# Core.net
KiCad netlist of a schematic drawn in Altium Designer
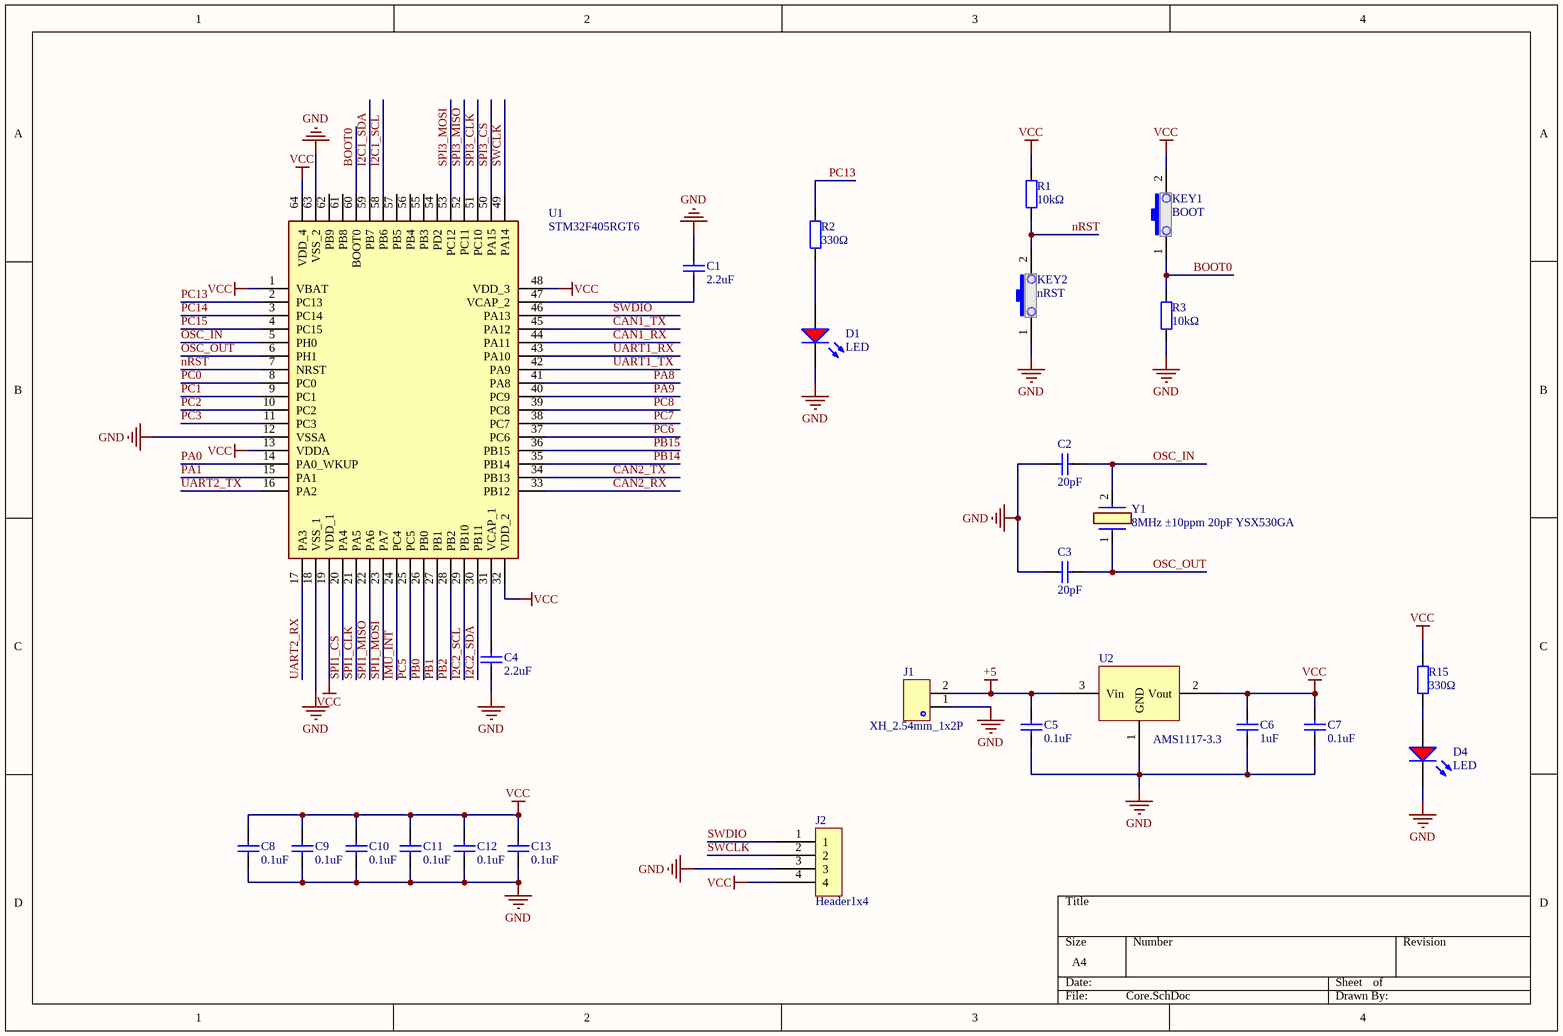
[diagram p0: Core.SchDoc]

(export (version "E")
  (design (tool "Eeschema 10.0.6"))
  (components
    (comp (ref "C1") (value "2.2uF") (footprint "C0603") (libsource (lib "NetTie") (part "Capacitor")))
    (comp (ref "C2") (value "20pF") (footprint "C0603") (libsource (lib "NetTie") (part "Capacitor")))
    (comp (ref "C3") (value "20pF") (footprint "C0603") (libsource (lib "NetTie") (part "Capacitor")))
    (comp (ref "C4") (value "2.2uF") (footprint "C0603") (libsource (lib "NetTie") (part "Capacitor")))
    (comp (ref "C5") (value "0.1uF") (footprint "C0603") (libsource (lib "NetTie") (part "Capacitor")))
    (comp (ref "C6") (value "1uF") (footprint "C0603") (libsource (lib "NetTie") (part "Capacitor")))
    (comp (ref "C7") (value "0.1uF") (footprint "C0603") (libsource (lib "NetTie") (part "Capacitor")))
    (comp (ref "C8") (value "0.1uF") (footprint "C0603") (libsource (lib "NetTie") (part "Capacitor")))
    (comp (ref "C9") (value "0.1uF") (footprint "C0603") (libsource (lib "NetTie") (part "Capacitor")))
    (comp (ref "C10") (value "0.1uF") (footprint "C0603") (libsource (lib "NetTie") (part "Capacitor")))
    (comp (ref "C11") (value "0.1uF") (footprint "C0603") (libsource (lib "NetTie") (part "Capacitor")))
    (comp (ref "C12") (value "0.1uF") (footprint "C0603") (libsource (lib "NetTie") (part "Capacitor")))
    (comp (ref "C13") (value "0.1uF") (footprint "C0603") (libsource (lib "NetTie") (part "Capacitor")))
    (comp (ref "D1")
      (value "LED")
      (footprint "0603_LED_S1")
      (description "发光二极管")
      (libsource (lib "LED") (part "0603 红灯"))
    )
    (comp (ref "D4")
      (value "LED")
      (footprint "0603_LED_S1")
      (description "发光二极管")
      (libsource (lib "LED") (part "0603 红灯"))
    )
    (comp (ref "J1")
      (value "XH_2.54mm_1x2P")
      (footprint "XH2.54mm1x2P弯插")
      (libsource (lib "NetTie") (part "XH_2.54mm_1x2P"))
    )
    (comp (ref "J2")
      (value "Header1x4")
      (footprint "Header 1x4p")
      (libsource (lib "Connectors") (part "Header1x4"))
    )
    (comp (ref "KEY1")
      (value "BOOT")
      (footprint "KEY_3*4")
      (description "C707339")
      (libsource (lib "NetTie") (part "KEY_3*4"))
    )
    (comp (ref "KEY2")
      (value "nRST")
      (footprint "KEY_3*4")
      (description "C707339")
      (libsource (lib "NetTie") (part "KEY_3*4"))
    )
    (comp (ref "R1") (value "10kΩ") (footprint "R0603") (libsource (lib "NetTie") (part "Resistor")))
    (comp (ref "R2") (value "330Ω") (footprint "R0603") (libsource (lib "") (part "Resistor_1")))
    (comp (ref "R3") (value "10kΩ") (footprint "R0603") (libsource (lib "NetTie") (part "Resistor")))
    (comp (ref "R15") (value "330Ω") (footprint "R0603") (libsource (lib "") (part "Resistor_1")))
    (comp (ref "U1")
      (value "STM32F405RGT6")
      (footprint "SamacSys:QFP50P1200X1200X160-64N")
      (description "Integrated Circuit")
      (fields
        (field (name "MANUFACTURER_PART_NUMBER") "STM32F405RGT6TR")
        (field (name "MOUSER PART NUMBER") "511-STM32F405RGT6TR")
      )
      (libsource (lib "*") (part "STM32F405RGT6TR"))
    )
    (comp (ref "U2")
      (value "AMS1117-3.3")
      (footprint "SOT-223")
      (description "C347222")
      (libsource (lib "PowerICs") (part "AMS1117-3.3"))
    )
    (comp (ref "Y1")
      (value "8MHz ±10ppm 20pF YSX530GA")
      (footprint "SamacSys:X503212MSB2GI")
      (description "Crystal or Oscillator")
      (fields (field (name "MANUFACTURER_PART_NUMBER") "X503212MSB2GI"))
      (libsource (lib "*") (part "X503212MSB2GI"))
    )
  )
  (nets
    (net (code "1") (name "+5") (class "Default")
      (node (ref "C5") (pin "2") (pinfunction "2_2") (pintype "passive"))
      (node (ref "J1") (pin "2") (pinfunction "2_2") (pintype "passive"))
      (node (ref "U2") (pin "3") (pinfunction "Vin_3") (pintype "passive"))
    )
    (net (code "2") (name "/BOOT0") (class "Default")
      (node (ref "KEY1") (pin "1") (pinfunction "1_1") (pintype "passive"))
      (node (ref "R3") (pin "2") (pinfunction "2_2") (pintype "passive"))
      (node (ref "U1") (pin "60") (pinfunction "BOOT0_60") (pintype "passive"))
    )
    (net (code "3") (name "/CAN1_RX") (class "Default")
      (node (ref "U1") (pin "44") (pinfunction "PA11_44") (pintype "passive"))
    )
    (net (code "4") (name "/CAN1_TX") (class "Default")
      (node (ref "U1") (pin "45") (pinfunction "PA12_45") (pintype "passive"))
    )
    (net (code "5") (name "/CAN2_RX") (class "Default")
      (node (ref "U1") (pin "33") (pinfunction "PB12_33") (pintype "passive"))
    )
    (net (code "6") (name "/CAN2_TX") (class "Default")
      (node (ref "U1") (pin "34") (pinfunction "PB13_34") (pintype "passive"))
    )
    (net (code "7") (name "/I2C1_SCL") (class "Default")
      (node (ref "U1") (pin "58") (pinfunction "PB6_58") (pintype "passive"))
    )
    (net (code "8") (name "/I2C1_SDA") (class "Default")
      (node (ref "U1") (pin "59") (pinfunction "PB7_59") (pintype "passive"))
    )
    (net (code "9") (name "/I2C2_SCL") (class "Default")
      (node (ref "U1") (pin "29") (pinfunction "PB10_29") (pintype "passive"))
    )
    (net (code "10") (name "/I2C2_SDA") (class "Default")
      (node (ref "U1") (pin "30") (pinfunction "PB11_30") (pintype "passive"))
    )
    (net (code "11") (name "/IMU_INT") (class "Default")
      (node (ref "U1") (pin "24") (pinfunction "PC4_24") (pintype "passive"))
    )
    (net (code "12") (name "/OSC_IN") (class "Default")
      (node (ref "C2") (pin "1") (pinfunction "1_1") (pintype "passive"))
      (node (ref "U1") (pin "5") (pinfunction "PH0_5") (pintype "passive"))
      (node (ref "Y1") (pin "2") (pinfunction "2_2") (pintype "passive"))
    )
    (net (code "13") (name "/OSC_OUT") (class "Default")
      (node (ref "C3") (pin "1") (pinfunction "1_1") (pintype "passive"))
      (node (ref "U1") (pin "6") (pinfunction "PH1_6") (pintype "passive"))
      (node (ref "Y1") (pin "1") (pinfunction "1_1") (pintype "passive"))
    )
    (net (code "14") (name "/PA0") (class "Default")
      (node (ref "U1") (pin "14") (pinfunction "PA0_WKUP_14") (pintype "passive"))
    )
    (net (code "15") (name "/PA1") (class "Default")
      (node (ref "U1") (pin "15") (pinfunction "PA1_15") (pintype "passive"))
    )
    (net (code "16") (name "/PA8") (class "Default")
      (node (ref "U1") (pin "41") (pinfunction "PA8_41") (pintype "passive"))
    )
    (net (code "17") (name "/PA9") (class "Default")
      (node (ref "U1") (pin "40") (pinfunction "PC9_40") (pintype "passive"))
    )
    (net (code "18") (name "/PB0") (class "Default")
      (node (ref "U1") (pin "26") (pinfunction "PB0_26") (pintype "passive"))
    )
    (net (code "19") (name "/PB1") (class "Default")
      (node (ref "U1") (pin "27") (pinfunction "PB1_27") (pintype "passive"))
    )
    (net (code "20") (name "/PB2") (class "Default")
      (node (ref "U1") (pin "28") (pinfunction "PB2_28") (pintype "passive"))
    )
    (net (code "21") (name "/PB14") (class "Default")
      (node (ref "U1") (pin "35") (pinfunction "PB14_35") (pintype "passive"))
    )
    (net (code "22") (name "/PB15") (class "Default")
      (node (ref "U1") (pin "36") (pinfunction "PB15_36") (pintype "passive"))
    )
    (net (code "23") (name "/PC0") (class "Default")
      (node (ref "U1") (pin "8") (pinfunction "PC0_8") (pintype "passive"))
    )
    (net (code "24") (name "/PC1") (class "Default")
      (node (ref "U1") (pin "9") (pinfunction "PC1_9") (pintype "passive"))
    )
    (net (code "25") (name "/PC2") (class "Default")
      (node (ref "U1") (pin "10") (pinfunction "PC2_10") (pintype "passive"))
    )
    (net (code "26") (name "/PC3") (class "Default")
      (node (ref "U1") (pin "11") (pinfunction "PC3_11") (pintype "passive"))
    )
    (net (code "27") (name "/PC5") (class "Default")
      (node (ref "U1") (pin "25") (pinfunction "PC5_25") (pintype "passive"))
    )
    (net (code "28") (name "/PC6") (class "Default")
      (node (ref "U1") (pin "37") (pinfunction "PC6_37") (pintype "passive"))
    )
    (net (code "29") (name "/PC7") (class "Default")
      (node (ref "U1") (pin "38") (pinfunction "PC7_38") (pintype "passive"))
    )
    (net (code "30") (name "/PC8") (class "Default")
      (node (ref "U1") (pin "39") (pinfunction "PC8_39") (pintype "passive"))
    )
    (net (code "31") (name "/PC13") (class "Default")
      (node (ref "R2") (pin "1") (pinfunction "1_1") (pintype "passive"))
      (node (ref "U1") (pin "2") (pinfunction "PC13_2") (pintype "passive"))
    )
    (net (code "32") (name "/PC14") (class "Default")
      (node (ref "U1") (pin "3") (pinfunction "PC14_3") (pintype "passive"))
    )
    (net (code "33") (name "/PC15") (class "Default")
      (node (ref "U1") (pin "4") (pinfunction "PC15_4") (pintype "passive"))
    )
    (net (code "34") (name "/SPI1_CLK") (class "Default")
      (node (ref "U1") (pin "21") (pinfunction "PA5_21") (pintype "passive"))
    )
    (net (code "35") (name "/SPI1_CS") (class "Default")
      (node (ref "U1") (pin "20") (pinfunction "PA4_20") (pintype "passive"))
    )
    (net (code "36") (name "/SPI1_MISO") (class "Default")
      (node (ref "U1") (pin "22") (pinfunction "PA6_22") (pintype "passive"))
    )
    (net (code "37") (name "/SPI1_MOSI") (class "Default")
      (node (ref "U1") (pin "23") (pinfunction "PA7_23") (pintype "passive"))
    )
    (net (code "38") (name "/SPI3_CLK") (class "Default")
      (node (ref "U1") (pin "51") (pinfunction "PC10_51") (pintype "passive"))
    )
    (net (code "39") (name "/SPI3_CS") (class "Default")
      (node (ref "U1") (pin "50") (pinfunction "PA15_50") (pintype "passive"))
    )
    (net (code "40") (name "/SPI3_MISO") (class "Default")
      (node (ref "U1") (pin "52") (pinfunction "PC11_52") (pintype "passive"))
    )
    (net (code "41") (name "/SPI3_MOSI") (class "Default")
      (node (ref "U1") (pin "53") (pinfunction "PC12_53") (pintype "passive"))
    )
    (net (code "42") (name "/SWCLK") (class "Default")
      (node (ref "J2") (pin "2") (pinfunction "2_2") (pintype "passive"))
      (node (ref "U1") (pin "49") (pinfunction "PA14_49") (pintype "passive"))
    )
    (net (code "43") (name "/SWDIO") (class "Default")
      (node (ref "J2") (pin "1") (pinfunction "1_1") (pintype "passive"))
      (node (ref "U1") (pin "46") (pinfunction "PA13_46") (pintype "passive"))
    )
    (net (code "44") (name "/UART1_RX") (class "Default")
      (node (ref "U1") (pin "43") (pinfunction "PA10_43") (pintype "passive"))
    )
    (net (code "45") (name "/UART1_TX") (class "Default")
      (node (ref "U1") (pin "42") (pinfunction "PA9_42") (pintype "passive"))
    )
    (net (code "46") (name "/UART2_RX") (class "Default")
      (node (ref "U1") (pin "17") (pinfunction "PA3_17") (pintype "passive"))
    )
    (net (code "47") (name "/UART2_TX") (class "Default")
      (node (ref "U1") (pin "16") (pinfunction "PA2_16") (pintype "passive"))
    )
    (net (code "48") (name "/nRST") (class "Default")
      (node (ref "KEY2") (pin "2") (pinfunction "2_2") (pintype "passive"))
      (node (ref "R1") (pin "1") (pinfunction "1_1") (pintype "passive"))
      (node (ref "U1") (pin "7") (pinfunction "NRST_7") (pintype "passive"))
    )
    (net (code "49") (name "GND") (class "Default")
      (node (ref "C1") (pin "2") (pinfunction "2_2") (pintype "passive"))
      (node (ref "C10") (pin "1") (pinfunction "1_1") (pintype "passive"))
      (node (ref "C11") (pin "1") (pinfunction "1_1") (pintype "passive"))
      (node (ref "C12") (pin "1") (pinfunction "1_1") (pintype "passive"))
      (node (ref "C13") (pin "1") (pinfunction "1_1") (pintype "passive"))
      (node (ref "C2") (pin "2") (pinfunction "2_2") (pintype "passive"))
      (node (ref "C3") (pin "2") (pinfunction "2_2") (pintype "passive"))
      (node (ref "C4") (pin "2") (pinfunction "2_2") (pintype "passive"))
      (node (ref "C5") (pin "1") (pinfunction "1_1") (pintype "passive"))
      (node (ref "C6") (pin "1") (pinfunction "1_1") (pintype "passive"))
      (node (ref "C7") (pin "1") (pinfunction "1_1") (pintype "passive"))
      (node (ref "C8") (pin "1") (pinfunction "1_1") (pintype "passive"))
      (node (ref "C9") (pin "1") (pinfunction "1_1") (pintype "passive"))
      (node (ref "D1") (pin "K") (pinfunction "K_K") (pintype "passive"))
      (node (ref "D4") (pin "K") (pinfunction "K_K") (pintype "passive"))
      (node (ref "J1") (pin "1") (pinfunction "1_1") (pintype "passive"))
      (node (ref "J2") (pin "3") (pinfunction "3_3") (pintype "passive"))
      (node (ref "KEY2") (pin "1") (pinfunction "1_1") (pintype "passive"))
      (node (ref "R3") (pin "1") (pinfunction "1_1") (pintype "passive"))
      (node (ref "U1") (pin "12") (pinfunction "VSSA_12") (pintype "passive"))
      (node (ref "U1") (pin "18") (pinfunction "VSS_1_18") (pintype "passive"))
      (node (ref "U1") (pin "63") (pinfunction "VSS_2_63") (pintype "passive"))
      (node (ref "U2") (pin "1") (pinfunction "GND_1") (pintype "passive"))
    )
    (net (code "50") (name "Net-(D1-PadA)") (class "Default")
      (node (ref "D1") (pin "A") (pinfunction "A_A") (pintype "passive"))
      (node (ref "R2") (pin "2") (pinfunction "2_2") (pintype "passive"))
    )
    (net (code "51") (name "Net-(D4-PadA)") (class "Default")
      (node (ref "D4") (pin "A") (pinfunction "A_A") (pintype "passive"))
      (node (ref "R15") (pin "2") (pinfunction "2_2") (pintype "passive"))
    )
    (net (code "52") (name "Net-(U1-VCAP_1)") (class "Default")
      (node (ref "C4") (pin "1") (pinfunction "1_1") (pintype "passive"))
      (node (ref "U1") (pin "31") (pinfunction "VCAP_1_31") (pintype "passive"))
    )
    (net (code "53") (name "Net-(U1-VCAP_2)") (class "Default")
      (node (ref "C1") (pin "1") (pinfunction "1_1") (pintype "passive"))
      (node (ref "U1") (pin "47") (pinfunction "VCAP_2_47") (pintype "passive"))
    )
    (net (code "54") (name "VCC") (class "Default")
      (node (ref "C10") (pin "2") (pinfunction "2_2") (pintype "passive"))
      (node (ref "C11") (pin "2") (pinfunction "2_2") (pintype "passive"))
      (node (ref "C12") (pin "2") (pinfunction "2_2") (pintype "passive"))
      (node (ref "C13") (pin "2") (pinfunction "2_2") (pintype "passive"))
      (node (ref "C6") (pin "2") (pinfunction "2_2") (pintype "passive"))
      (node (ref "C7") (pin "2") (pinfunction "2_2") (pintype "passive"))
      (node (ref "C8") (pin "2") (pinfunction "2_2") (pintype "passive"))
      (node (ref "C9") (pin "2") (pinfunction "2_2") (pintype "passive"))
      (node (ref "J2") (pin "4") (pinfunction "4_4") (pintype "passive"))
      (node (ref "KEY1") (pin "2") (pinfunction "2_2") (pintype "passive"))
      (node (ref "R1") (pin "2") (pinfunction "2_2") (pintype "passive"))
      (node (ref "R15") (pin "1") (pinfunction "1_1") (pintype "passive"))
      (node (ref "U1") (pin "1") (pinfunction "VBAT_1") (pintype "passive"))
      (node (ref "U1") (pin "13") (pinfunction "VDDA_13") (pintype "passive"))
      (node (ref "U1") (pin "19") (pinfunction "VDD_1_19") (pintype "passive"))
      (node (ref "U1") (pin "32") (pinfunction "VDD_2_32") (pintype "passive"))
      (node (ref "U1") (pin "48") (pinfunction "VDD_3_48") (pintype "passive"))
      (node (ref "U1") (pin "64") (pinfunction "VDD_4_64") (pintype "passive"))
      (node (ref "U2") (pin "2") (pinfunction "Vout_2") (pintype "passive"))
    )
    (net (code "55") (name "unconnected-(U1-PB3-Pad55)") (class "Default")
      (node (ref "U1") (pin "55") (pinfunction "PB3_55") (pintype "passive"))
    )
    (net (code "56") (name "unconnected-(U1-PB4-Pad56)") (class "Default")
      (node (ref "U1") (pin "56") (pinfunction "PB4_56") (pintype "passive"))
    )
    (net (code "57") (name "unconnected-(U1-PB5-Pad57)") (class "Default")
      (node (ref "U1") (pin "57") (pinfunction "PB5_57") (pintype "passive"))
    )
    (net (code "58") (name "unconnected-(U1-PB8-Pad61)") (class "Default")
      (node (ref "U1") (pin "61") (pinfunction "PB8_61") (pintype "passive"))
    )
    (net (code "59") (name "unconnected-(U1-PB9-Pad62)") (class "Default")
      (node (ref "U1") (pin "62") (pinfunction "PB9_62") (pintype "passive"))
    )
    (net (code "60") (name "unconnected-(U1-PD2-Pad54)") (class "Default")
      (node (ref "U1") (pin "54") (pinfunction "PD2_54") (pintype "passive"))
    )
  )
)
